# nano-SO2R.net
KiCad netlist of a schematic drawn in EAGLE
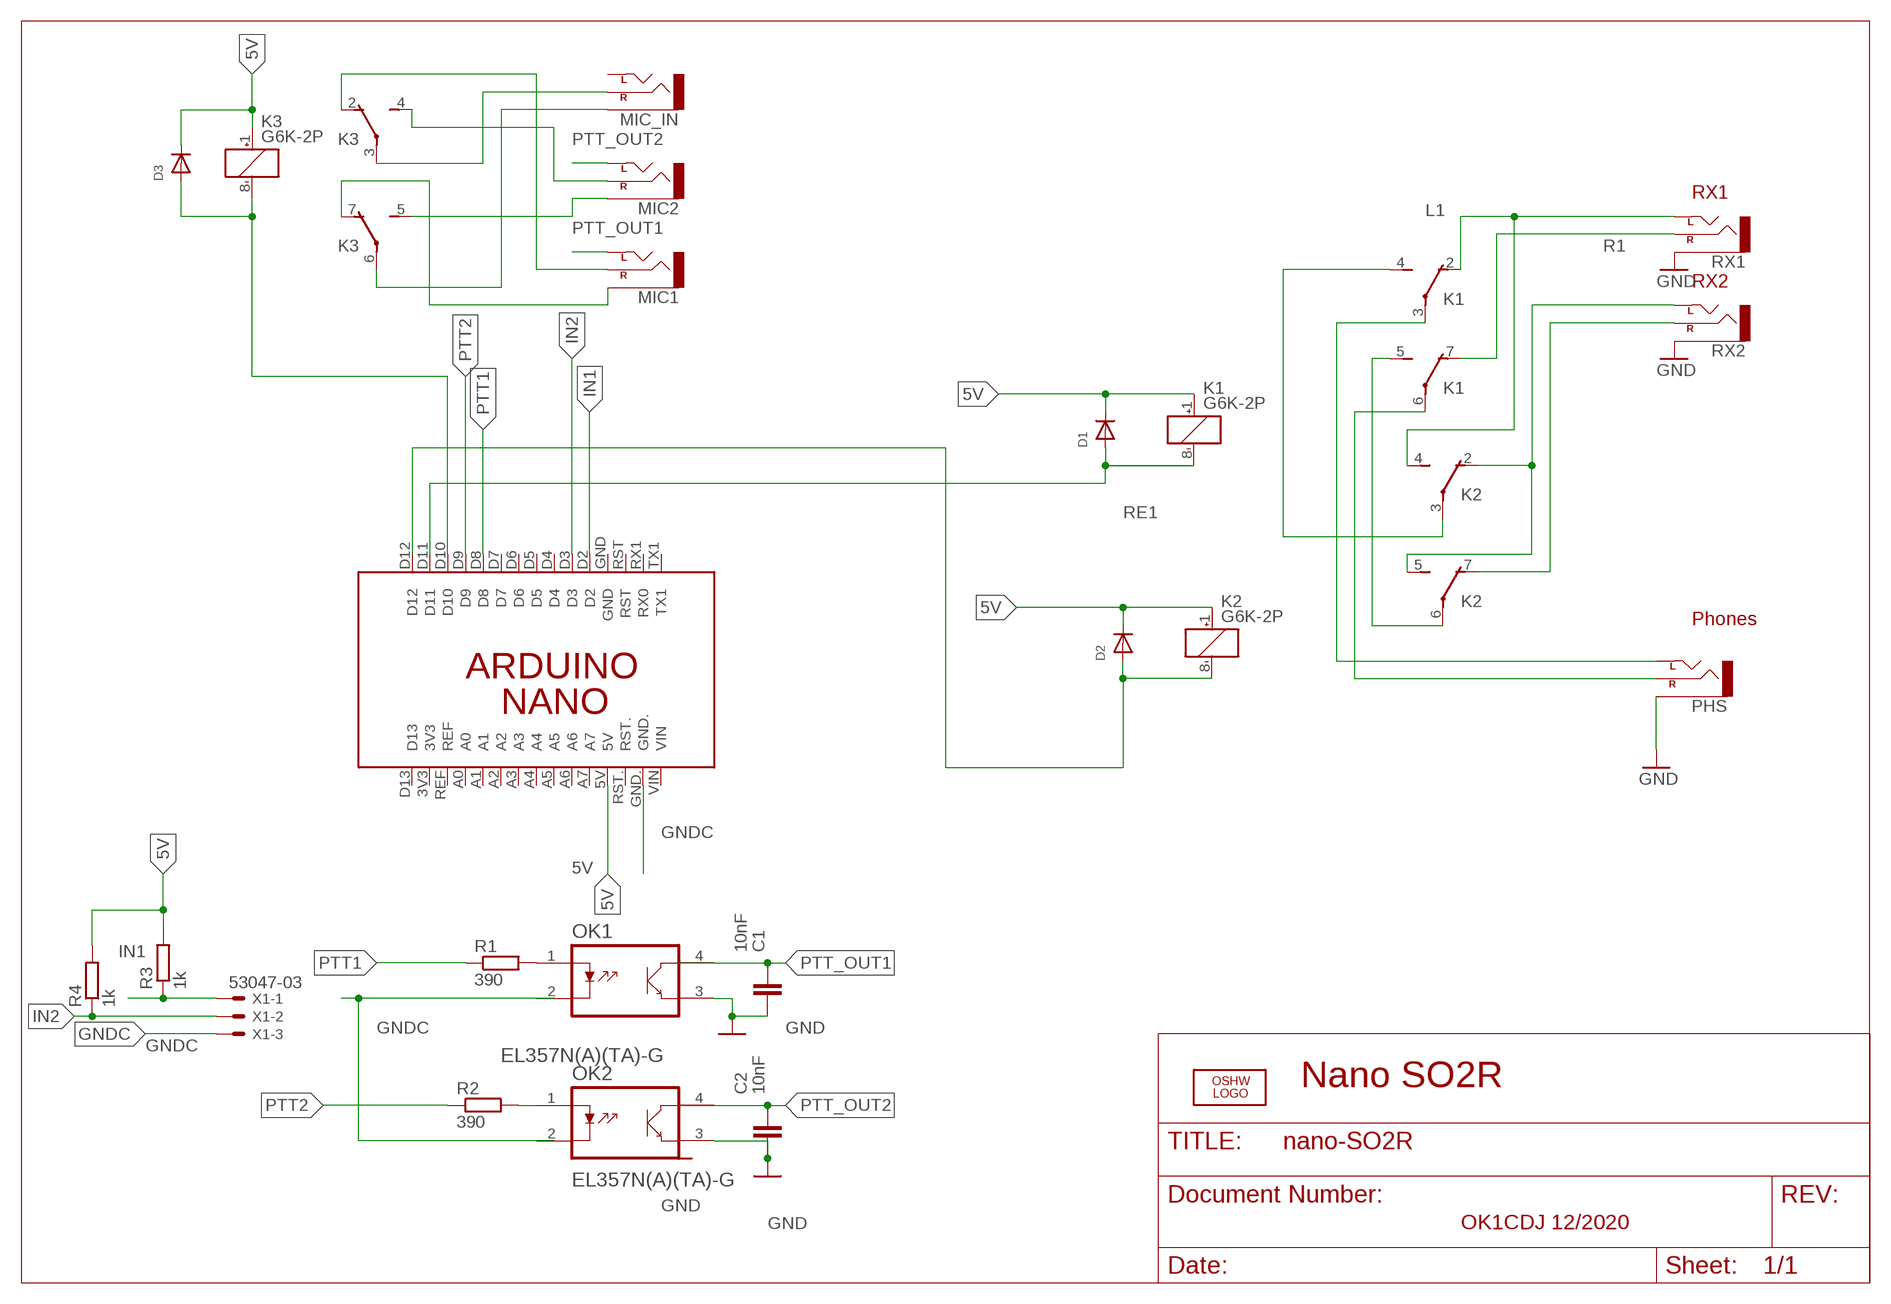
[diagram p0: schematic, sheet 1]

(export (version "E")
  (design (tool "Eeschema 10.0.6"))
  (components
    (comp (ref "C1")
      (value "10nF")
      (footprint "eagle-import:C0805")
      (libsource (lib "eagle-import") (part "C-EUC0805"))
    )
    (comp (ref "C2")
      (value "10nF")
      (footprint "eagle-import:C0805")
      (libsource (lib "eagle-import") (part "C-EUC0805"))
    )
    (comp (ref "D1")
      (value "DIODESOD-323F")
      (footprint "eagle-import:SOD-323F")
      (libsource (lib "eagle-import") (part "DIODESOD-323F"))
    )
    (comp (ref "D2")
      (value "DIODESOD-323F")
      (footprint "eagle-import:SOD-323F")
      (libsource (lib "eagle-import") (part "DIODESOD-323F"))
    )
    (comp (ref "D3")
      (value "DIODESOD-323F")
      (footprint "eagle-import:SOD-323F")
      (libsource (lib "eagle-import") (part "DIODESOD-323F"))
    )
    (comp (ref "K1")
      (value "G6K-2P")
      (footprint "eagle-import:G6K-2P")
      (fields (field (name "MF") "OMRON COMPONENTS USA") (field (name "MPN") "G6K-2P DC3"))
      (libsource (lib "eagle-import") (part "G6K-2P"))
    )
    (comp (ref "K2")
      (value "G6K-2P")
      (footprint "eagle-import:G6K-2P")
      (fields (field (name "MF") "OMRON COMPONENTS USA") (field (name "MPN") "G6K-2P DC3"))
      (libsource (lib "eagle-import") (part "G6K-2P"))
    )
    (comp (ref "K3")
      (value "G6K-2P")
      (footprint "eagle-import:G6K-2P")
      (fields (field (name "MF") "OMRON COMPONENTS USA") (field (name "MPN") "G6K-2P DC3"))
      (libsource (lib "eagle-import") (part "G6K-2P"))
    )
    (comp (ref "LOGO1")
      (value "OSHW_LOGO_FILLX0150-NT")
      (footprint "eagle-import:OSHW_FILLX150_NOTEXT")
      (libsource (lib "eagle-import") (part "OSHW_LOGO_FILLX0150-NT"))
    )
    (comp (ref "MIC1")
      (value "MIC1")
      (footprint "eagle-import:AUDIO-JACK")
      (libsource (lib "eagle-import") (part "AUDIO-JACKPTH"))
    )
    (comp (ref "MIC2")
      (value "AUDIO-JACKPTH")
      (footprint "eagle-import:AUDIO-JACK")
      (libsource (lib "eagle-import") (part "AUDIO-JACKPTH"))
    )
    (comp (ref "MIC_IN")
      (value "AUDIO-JACKPTH")
      (footprint "eagle-import:AUDIO-JACK")
      (libsource (lib "eagle-import") (part "AUDIO-JACKPTH"))
    )
    (comp (ref "OK1")
      (value "EL357N(A)(TA)-G")
      (footprint "eagle-import:SOP254P700X200-4N")
      (fields (field (name "MF") "Everlight Electronics"))
      (libsource (lib "eagle-import") (part "EL357N(A)(TA)-G"))
    )
    (comp (ref "OK2")
      (value "EL357N(A)(TA)-G")
      (footprint "eagle-import:SOP254P700X200-4N")
      (fields (field (name "MF") "Everlight Electronics"))
      (libsource (lib "eagle-import") (part "EL357N(A)(TA)-G"))
    )
    (comp (ref "PCB1")
      (value "ARDUINO_NANO")
      (footprint "eagle-import:ARDUINO_NANO")
      (libsource (lib "eagle-import") (part "ARDUINO_NANO"))
    )
    (comp (ref "PHS")
      (value "AUDIO-JACKPTH")
      (footprint "eagle-import:AUDIO-JACK")
      (libsource (lib "eagle-import") (part "AUDIO-JACKPTH"))
    )
    (comp (ref "R1")
      (value "390")
      (footprint "eagle-import:M0805")
      (libsource (lib "eagle-import") (part "R-EU_M0805"))
    )
    (comp (ref "R2")
      (value "390")
      (footprint "eagle-import:M0805")
      (libsource (lib "eagle-import") (part "R-EU_M0805"))
    )
    (comp (ref "R3")
      (value "1k")
      (footprint "eagle-import:M0805")
      (libsource (lib "eagle-import") (part "R-EU_M0805"))
    )
    (comp (ref "R4")
      (value "1k")
      (footprint "eagle-import:M0805")
      (libsource (lib "eagle-import") (part "R-EU_M0805"))
    )
    (comp (ref "RX1")
      (value "AUDIO-JACKPTH")
      (footprint "eagle-import:AUDIO-JACK")
      (libsource (lib "eagle-import") (part "AUDIO-JACKPTH"))
    )
    (comp (ref "RX2")
      (value "AUDIO-JACKPTH")
      (footprint "eagle-import:AUDIO-JACK")
      (libsource (lib "eagle-import") (part "AUDIO-JACKPTH"))
    )
    (comp (ref "X1")
      (value "53047-03")
      (footprint "eagle-import:53047-03")
      (fields (field (name "MPN") "530470310"))
      (libsource (lib "eagle-import") (part "53?-03047"))
    )
  )
  (nets
    (net (code "1") (name "/L1") (class "Default")
      (node (ref "K1") (pin "2") (pinfunction "O_2") (pintype "passive"))
      (node (ref "K2") (pin "4") (pinfunction "S_4") (pintype "passive"))
      (node (ref "RX1") (pin "TIP") (pinfunction "LEFT_TIP") (pintype "bidirectional"))
    )
    (net (code "2") (name "/R1") (class "Default")
      (node (ref "K1") (pin "7") (pinfunction "O_7") (pintype "passive"))
      (node (ref "RX1") (pin "RING") (pinfunction "RIGHT_RING") (pintype "bidirectional"))
    )
    (net (code "3") (name "/RE1") (class "Default")
      (node (ref "D1") (pin "A") (pinfunction "A_A") (pintype "passive"))
      (node (ref "K1") (pin "8") (pinfunction "-_8") (pintype "passive"))
      (node (ref "PCB1") (pin "D11") (pinfunction "D11_D11") (pintype "bidirectional"))
    )
    (net (code "4") (name "5V") (class "Default")
      (node (ref "D1") (pin "C") (pinfunction "C_C") (pintype "passive"))
      (node (ref "D2") (pin "C") (pinfunction "C_C") (pintype "passive"))
      (node (ref "D3") (pin "C") (pinfunction "C_C") (pintype "passive"))
      (node (ref "K1") (pin "1") (pinfunction "+_1") (pintype "passive"))
      (node (ref "K2") (pin "1") (pinfunction "+_1") (pintype "passive"))
      (node (ref "K3") (pin "1") (pinfunction "+_1") (pintype "passive"))
      (node (ref "PCB1") (pin "5V") (pinfunction "5V_5V") (pintype "bidirectional"))
      (node (ref "R3") (pin "2") (pinfunction "2_2") (pintype "passive"))
      (node (ref "R4") (pin "2") (pinfunction "2_2") (pintype "passive"))
    )
    (net (code "5") (name "GND") (class "Default")
      (node (ref "C1") (pin "2") (pinfunction "2_2") (pintype "passive"))
      (node (ref "C2") (pin "2") (pinfunction "2_2") (pintype "passive"))
      (node (ref "OK1") (pin "3") (pinfunction "E_3") (pintype "passive"))
      (node (ref "OK2") (pin "3") (pinfunction "E_3") (pintype "passive"))
      (node (ref "PHS") (pin "SLEEVE") (pinfunction "SLEEVE_SLEEVE") (pintype "bidirectional"))
      (node (ref "RX1") (pin "SLEEVE") (pinfunction "SLEEVE_SLEEVE") (pintype "bidirectional"))
      (node (ref "RX2") (pin "SLEEVE") (pinfunction "SLEEVE_SLEEVE") (pintype "bidirectional"))
    )
    (net (code "6") (name "GNDC") (class "Default")
      (node (ref "OK1") (pin "2") (pinfunction "K_2") (pintype "passive"))
      (node (ref "OK2") (pin "2") (pinfunction "K_2") (pintype "passive"))
      (node (ref "PCB1") (pin "GND.") (pinfunction "GND._GND.") (pintype "bidirectional"))
      (node (ref "X1") (pin "3") (pinfunction "S_3") (pintype "passive"))
    )
    (net (code "7") (name "IN1") (class "Default")
      (node (ref "PCB1") (pin "D2") (pinfunction "D2_D2") (pintype "bidirectional"))
      (node (ref "R3") (pin "1") (pinfunction "1_1") (pintype "passive"))
      (node (ref "X1") (pin "1") (pinfunction "S_1") (pintype "passive"))
    )
    (net (code "8") (name "IN2") (class "Default")
      (node (ref "PCB1") (pin "D3") (pinfunction "D3_D3") (pintype "bidirectional"))
      (node (ref "R4") (pin "1") (pinfunction "1_1") (pintype "passive"))
      (node (ref "X1") (pin "2") (pinfunction "S_2") (pintype "passive"))
    )
    (net (code "9") (name "Net-(K1B-P)") (class "Default")
      (node (ref "K1") (pin "3") (pinfunction "P_3") (pintype "passive"))
      (node (ref "PHS") (pin "TIP") (pinfunction "LEFT_TIP") (pintype "bidirectional"))
    )
    (net (code "10") (name "Net-(K1B-S)") (class "Default")
      (node (ref "K1") (pin "4") (pinfunction "S_4") (pintype "passive"))
      (node (ref "K2") (pin "3") (pinfunction "P_3") (pintype "passive"))
    )
    (net (code "11") (name "Net-(K1C-P)") (class "Default")
      (node (ref "K1") (pin "6") (pinfunction "P_6") (pintype "passive"))
      (node (ref "PHS") (pin "RING") (pinfunction "RIGHT_RING") (pintype "bidirectional"))
    )
    (net (code "12") (name "Net-(K1C-S)") (class "Default")
      (node (ref "K1") (pin "5") (pinfunction "S_5") (pintype "passive"))
      (node (ref "K2") (pin "6") (pinfunction "P_6") (pintype "passive"))
    )
    (net (code "13") (name "Net-(K2A--)") (class "Default")
      (node (ref "D2") (pin "A") (pinfunction "A_A") (pintype "passive"))
      (node (ref "K2") (pin "8") (pinfunction "-_8") (pintype "passive"))
      (node (ref "PCB1") (pin "D12") (pinfunction "D12_D12") (pintype "bidirectional"))
    )
    (net (code "14") (name "Net-(K2B-O)") (class "Default")
      (node (ref "K2") (pin "2") (pinfunction "O_2") (pintype "passive"))
      (node (ref "K2") (pin "5") (pinfunction "S_5") (pintype "passive"))
      (node (ref "RX2") (pin "TIP") (pinfunction "LEFT_TIP") (pintype "bidirectional"))
    )
    (net (code "15") (name "Net-(K2C-O)") (class "Default")
      (node (ref "K2") (pin "7") (pinfunction "O_7") (pintype "passive"))
      (node (ref "RX2") (pin "RING") (pinfunction "RIGHT_RING") (pintype "bidirectional"))
    )
    (net (code "16") (name "Net-(K3A--)") (class "Default")
      (node (ref "D3") (pin "A") (pinfunction "A_A") (pintype "passive"))
      (node (ref "K3") (pin "8") (pinfunction "-_8") (pintype "passive"))
      (node (ref "PCB1") (pin "D10") (pinfunction "D10_D10") (pintype "bidirectional"))
    )
    (net (code "17") (name "Net-(K3B-O)") (class "Default")
      (node (ref "K3") (pin "2") (pinfunction "O_2") (pintype "passive"))
      (node (ref "MIC1") (pin "RING") (pinfunction "RIGHT_RING") (pintype "bidirectional"))
    )
    (net (code "18") (name "Net-(K3B-P)") (class "Default")
      (node (ref "K3") (pin "3") (pinfunction "P_3") (pintype "passive"))
      (node (ref "MIC_IN") (pin "RING") (pinfunction "RIGHT_RING") (pintype "bidirectional"))
    )
    (net (code "19") (name "Net-(K3B-S)") (class "Default")
      (node (ref "K3") (pin "4") (pinfunction "S_4") (pintype "passive"))
      (node (ref "MIC2") (pin "RING") (pinfunction "RIGHT_RING") (pintype "bidirectional"))
    )
    (net (code "20") (name "Net-(K3C-O)") (class "Default")
      (node (ref "K3") (pin "7") (pinfunction "O_7") (pintype "passive"))
      (node (ref "MIC1") (pin "SLEEVE") (pinfunction "SLEEVE_SLEEVE") (pintype "bidirectional"))
    )
    (net (code "21") (name "Net-(K3C-P)") (class "Default")
      (node (ref "K3") (pin "6") (pinfunction "P_6") (pintype "passive"))
      (node (ref "MIC_IN") (pin "SLEEVE") (pinfunction "SLEEVE_SLEEVE") (pintype "bidirectional"))
    )
    (net (code "22") (name "Net-(K3C-S)") (class "Default")
      (node (ref "K3") (pin "5") (pinfunction "S_5") (pintype "passive"))
      (node (ref "MIC2") (pin "SLEEVE") (pinfunction "SLEEVE_SLEEVE") (pintype "bidirectional"))
    )
    (net (code "23") (name "Net-(OK1-A)") (class "Default")
      (node (ref "OK1") (pin "1") (pinfunction "A_1") (pintype "passive"))
      (node (ref "R1") (pin "2") (pinfunction "2_2") (pintype "passive"))
    )
    (net (code "24") (name "Net-(OK2-A)") (class "Default")
      (node (ref "OK2") (pin "1") (pinfunction "A_1") (pintype "passive"))
      (node (ref "R2") (pin "2") (pinfunction "2_2") (pintype "passive"))
    )
    (net (code "25") (name "PTT1") (class "Default")
      (node (ref "PCB1") (pin "D8") (pinfunction "D8_D8") (pintype "bidirectional"))
      (node (ref "R1") (pin "1") (pinfunction "1_1") (pintype "passive"))
    )
    (net (code "26") (name "PTT2") (class "Default")
      (node (ref "PCB1") (pin "D9") (pinfunction "D9_D9") (pintype "bidirectional"))
      (node (ref "R2") (pin "1") (pinfunction "1_1") (pintype "passive"))
    )
    (net (code "27") (name "PTT_OUT1") (class "Default")
      (node (ref "C1") (pin "1") (pinfunction "1_1") (pintype "passive"))
      (node (ref "MIC1") (pin "TIP") (pinfunction "LEFT_TIP") (pintype "bidirectional"))
      (node (ref "OK1") (pin "4") (pinfunction "C_4") (pintype "passive"))
    )
    (net (code "28") (name "PTT_OUT2") (class "Default")
      (node (ref "C2") (pin "1") (pinfunction "1_1") (pintype "passive"))
      (node (ref "MIC2") (pin "TIP") (pinfunction "LEFT_TIP") (pintype "bidirectional"))
      (node (ref "OK2") (pin "4") (pinfunction "C_4") (pintype "passive"))
    )
    (net (code "29") (name "unconnected-(MIC_IN-LEFT-PadTIP)") (class "Default")
      (node (ref "MIC_IN") (pin "TIP") (pinfunction "LEFT_TIP") (pintype "bidirectional"))
    )
    (net (code "30") (name "unconnected-(PCB1-Pad3V3)") (class "Default")
      (node (ref "PCB1") (pin "3V3") (pinfunction "3V3_3V3") (pintype "bidirectional"))
    )
    (net (code "31") (name "unconnected-(PCB1-PadA0)") (class "Default")
      (node (ref "PCB1") (pin "A0") (pinfunction "A0_A0") (pintype "bidirectional"))
    )
    (net (code "32") (name "unconnected-(PCB1-PadA1)") (class "Default")
      (node (ref "PCB1") (pin "A1") (pinfunction "A1_A1") (pintype "bidirectional"))
    )
    (net (code "33") (name "unconnected-(PCB1-PadA2)") (class "Default")
      (node (ref "PCB1") (pin "A2") (pinfunction "A2_A2") (pintype "bidirectional"))
    )
    (net (code "34") (name "unconnected-(PCB1-PadA3)") (class "Default")
      (node (ref "PCB1") (pin "A3") (pinfunction "A3_A3") (pintype "bidirectional"))
    )
    (net (code "35") (name "unconnected-(PCB1-PadA4)") (class "Default")
      (node (ref "PCB1") (pin "A4") (pinfunction "A4_A4") (pintype "bidirectional"))
    )
    (net (code "36") (name "unconnected-(PCB1-PadA5)") (class "Default")
      (node (ref "PCB1") (pin "A5") (pinfunction "A5_A5") (pintype "bidirectional"))
    )
    (net (code "37") (name "unconnected-(PCB1-PadA6)") (class "Default")
      (node (ref "PCB1") (pin "A6") (pinfunction "A6_A6") (pintype "bidirectional"))
    )
    (net (code "38") (name "unconnected-(PCB1-PadA7)") (class "Default")
      (node (ref "PCB1") (pin "A7") (pinfunction "A7_A7") (pintype "bidirectional"))
    )
    (net (code "39") (name "unconnected-(PCB1-PadD4)") (class "Default")
      (node (ref "PCB1") (pin "D4") (pinfunction "D4_D4") (pintype "bidirectional"))
    )
    (net (code "40") (name "unconnected-(PCB1-PadD5)") (class "Default")
      (node (ref "PCB1") (pin "D5") (pinfunction "D5_D5") (pintype "bidirectional"))
    )
    (net (code "41") (name "unconnected-(PCB1-PadD6)") (class "Default")
      (node (ref "PCB1") (pin "D6") (pinfunction "D6_D6") (pintype "bidirectional"))
    )
    (net (code "42") (name "unconnected-(PCB1-PadD7)") (class "Default")
      (node (ref "PCB1") (pin "D7") (pinfunction "D7_D7") (pintype "bidirectional"))
    )
    (net (code "43") (name "unconnected-(PCB1-PadD13)") (class "Default")
      (node (ref "PCB1") (pin "D13") (pinfunction "D13_D13") (pintype "bidirectional"))
    )
    (net (code "44") (name "unconnected-(PCB1-PadGND)") (class "Default")
      (node (ref "PCB1") (pin "GND") (pinfunction "GND_GND") (pintype "bidirectional"))
    )
    (net (code "45") (name "unconnected-(PCB1-PadREF)") (class "Default")
      (node (ref "PCB1") (pin "REF") (pinfunction "REF_REF") (pintype "bidirectional"))
    )
    (net (code "46") (name "unconnected-(PCB1-PadRST)") (class "Default")
      (node (ref "PCB1") (pin "RST") (pinfunction "RST_RST") (pintype "bidirectional"))
    )
    (net (code "47") (name "unconnected-(PCB1-PadRST.)") (class "Default")
      (node (ref "PCB1") (pin "RST.") (pinfunction "RST._RST.") (pintype "bidirectional"))
    )
    (net (code "48") (name "unconnected-(PCB1-PadTX1)") (class "Default")
      (node (ref "PCB1") (pin "TX1") (pinfunction "TX1_TX1") (pintype "bidirectional"))
    )
    (net (code "49") (name "unconnected-(PCB1-PadVIN)") (class "Default")
      (node (ref "PCB1") (pin "VIN") (pinfunction "VIN_VIN") (pintype "bidirectional"))
    )
    (net (code "50") (name "unconnected-(PCB1-RX0-PadRX1)") (class "Default")
      (node (ref "PCB1") (pin "RX1") (pinfunction "RX0_RX1") (pintype "bidirectional"))
    )
  )
)
